# hw2.net
KiCad netlist of a schematic drawn in EAGLE
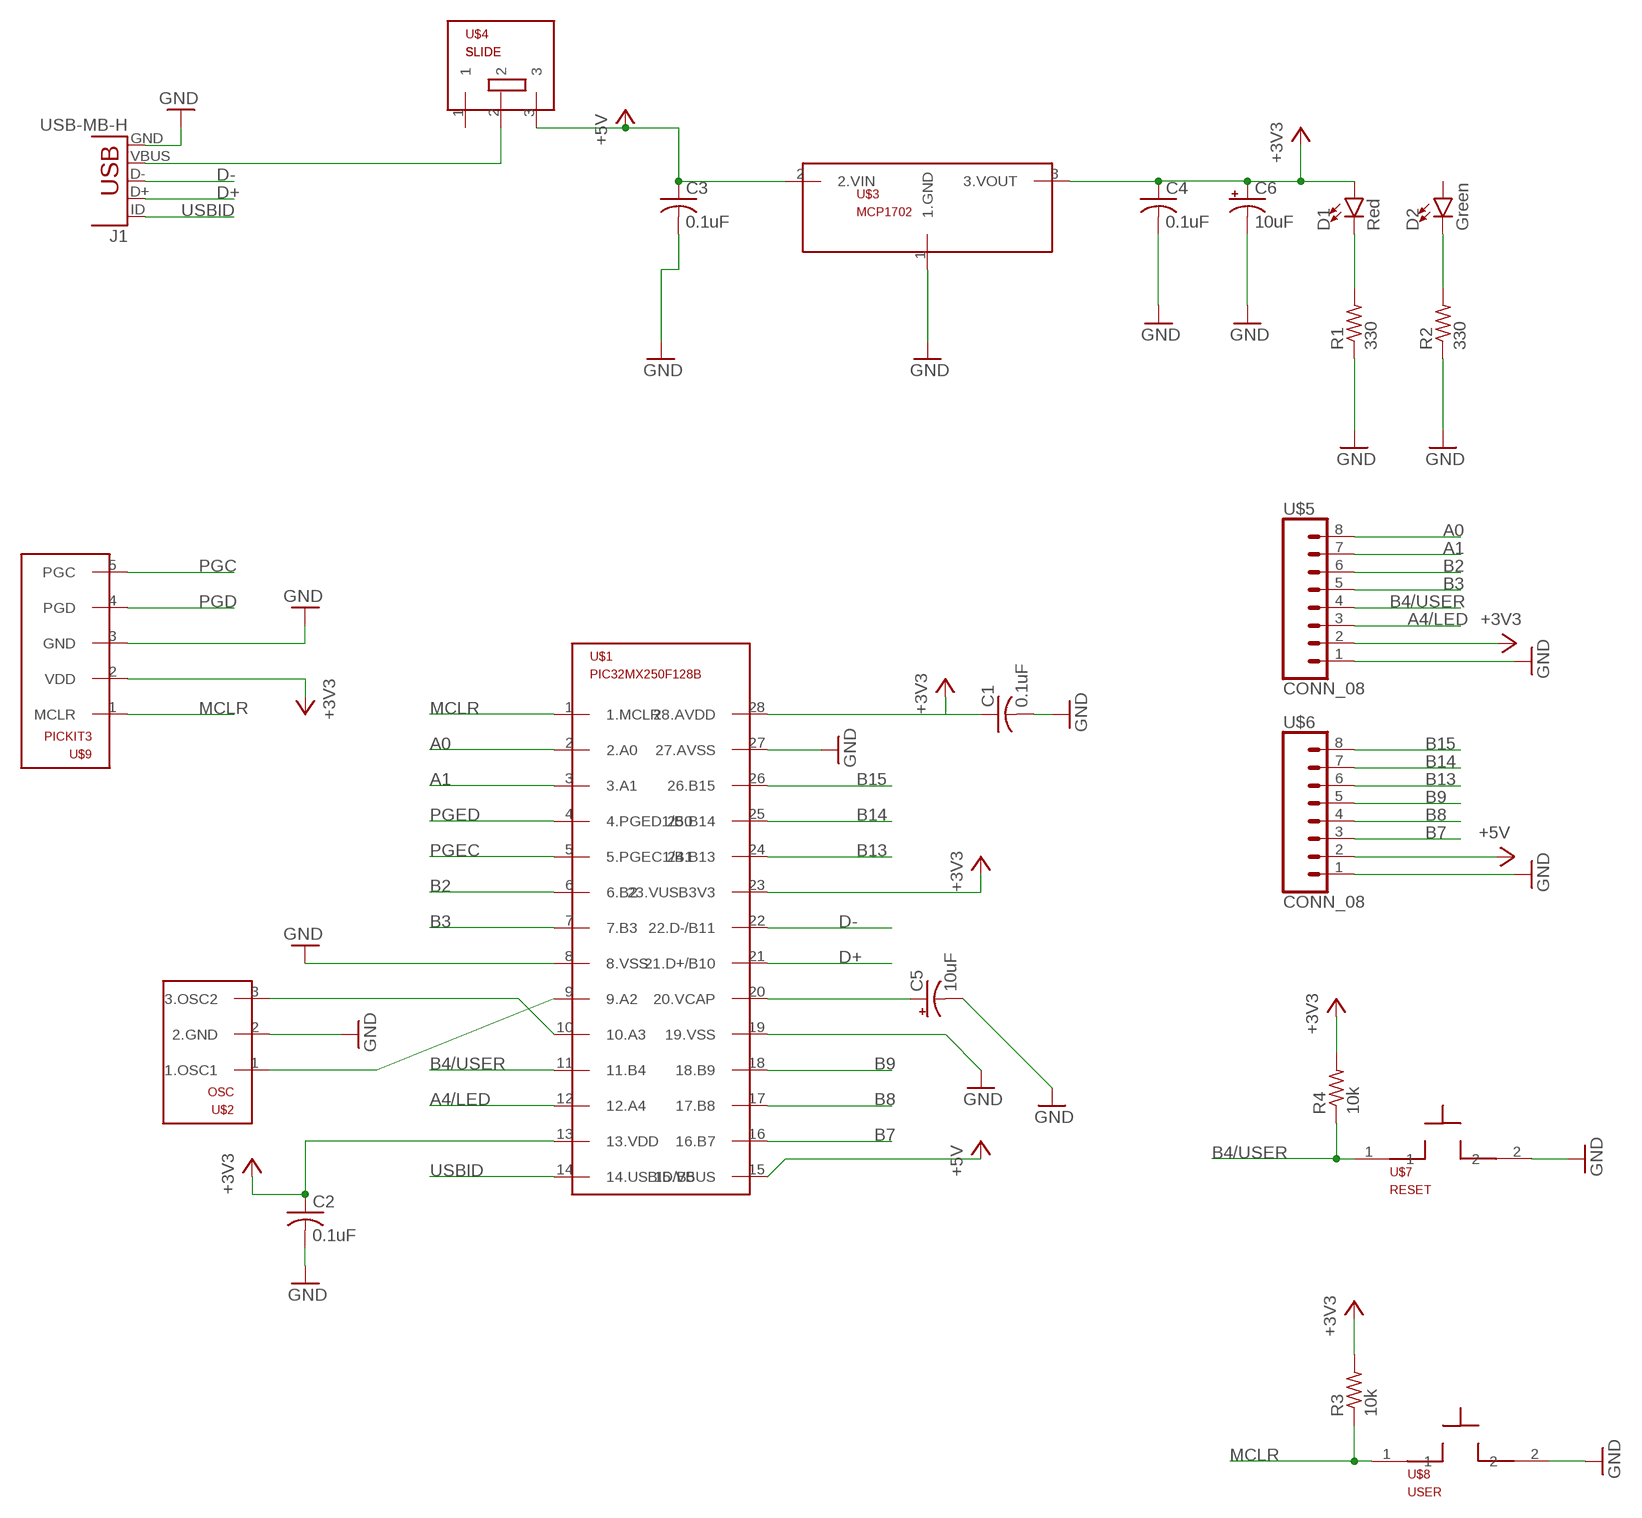
[diagram p0: schematic, sheet 1]

(export (version "E")
  (design (tool "Eeschema 10.0.6"))
  (components
    (comp (ref "C1")
      (value "0.1uF")
      (footprint "eagle-import:C025-025X050")
      (libsource (lib "eagle-import") (part "C-US025-025X050"))
    )
    (comp (ref "C2")
      (value "0.1uF")
      (footprint "eagle-import:C025-025X050")
      (libsource (lib "eagle-import") (part "C-US025-025X050"))
    )
    (comp (ref "C3")
      (value "0.1uF")
      (footprint "eagle-import:C025-025X050")
      (fields (field (name "SPICEPREFIX") "0.1uF"))
      (libsource (lib "eagle-import") (part "C-US025-025X050"))
    )
    (comp (ref "C4")
      (value "0.1uF")
      (footprint "eagle-import:C025-025X050")
      (libsource (lib "eagle-import") (part "C-US025-025X050"))
    )
    (comp (ref "C5")
      (value "10uF")
      (footprint "eagle-import:B45181B")
      (libsource (lib "eagle-import") (part "CPOL-USB45181B"))
    )
    (comp (ref "C6")
      (value "10uF")
      (footprint "eagle-import:B45181B")
      (libsource (lib "eagle-import") (part "CPOL-USB45181B"))
    )
    (comp (ref "D1")
      (value "Red")
      (footprint "eagle-import:LED_3MM")
      (libsource (lib "eagle-import") (part "LED3MM"))
    )
    (comp (ref "D2")
      (value "Green")
      (footprint "eagle-import:LED_3MM")
      (libsource (lib "eagle-import") (part "LED3MM"))
    )
    (comp (ref "J1")
      (value "USB-MB-H")
      (footprint "eagle-import:USB-MB-H")
      (libsource (lib "eagle-import") (part "USB-MB-H"))
    )
    (comp (ref "R1")
      (value "330")
      (footprint "eagle-import:0207_10")
      (libsource (lib "eagle-import") (part "R-US_0207/10"))
    )
    (comp (ref "R2")
      (value "330")
      (footprint "eagle-import:0207_10")
      (libsource (lib "eagle-import") (part "R-US_0207/10"))
    )
    (comp (ref "R3")
      (value "10k")
      (footprint "eagle-import:0207_10")
      (libsource (lib "eagle-import") (part "R-US_0207/10"))
    )
    (comp (ref "R4")
      (value "10k")
      (footprint "eagle-import:0207_10")
      (libsource (lib "eagle-import") (part "R-US_0207/10"))
    )
    (comp (ref "U$1")
      (value "PIC32MX250F128B")
      (footprint "eagle-import:DIL28-3")
      (libsource (lib "eagle-import") (part "PIC32MX250F128B"))
    )
    (comp (ref "U$2")
      (value "OSC")
      (footprint "eagle-import:OSC")
      (libsource (lib "eagle-import") (part "OSC"))
    )
    (comp (ref "U$3")
      (value "MCP1702")
      (footprint "eagle-import:TO92")
      (libsource (lib "eagle-import") (part "MCP1702"))
    )
    (comp (ref "U$4")
      (value "SLIDE")
      (footprint "eagle-import:SLIDE")
      (libsource (lib "eagle-import") (part "SLIDE"))
    )
    (comp (ref "U$5")
      (value "CONN_08")
      (footprint "eagle-import:1X08")
      (libsource (lib "eagle-import") (part "CONN_08"))
    )
    (comp (ref "U$6")
      (value "CONN_08")
      (footprint "eagle-import:1X08")
      (libsource (lib "eagle-import") (part "CONN_08"))
    )
    (comp (ref "U$7")
      (value "RESET")
      (footprint "eagle-import:PB")
      (libsource (lib "eagle-import") (part "PB"))
    )
    (comp (ref "U$8")
      (value "USER")
      (footprint "eagle-import:PB")
      (libsource (lib "eagle-import") (part "PB"))
    )
    (comp (ref "U$9")
      (value "PICKIT3")
      (footprint "eagle-import:1X05")
      (libsource (lib "eagle-import") (part "PICKIT3"))
    )
  )
  (nets
    (net (code "1") (name "+3V3") (class "Default")
      (node (ref "C2") (pin "1") (pinfunction "1_1") (pintype "passive"))
      (node (ref "C4") (pin "1") (pinfunction "1_1") (pintype "passive"))
      (node (ref "C6") (pin "+") (pinfunction "+_+") (pintype "passive"))
      (node (ref "D1") (pin "A") (pinfunction "A_A") (pintype "passive"))
      (node (ref "R3") (pin "2") (pinfunction "2_2") (pintype "passive"))
      (node (ref "R4") (pin "2") (pinfunction "2_2") (pintype "passive"))
      (node (ref "U$1") (pin "13") (pinfunction "13.VDD_13") (pintype "bidirectional"))
      (node (ref "U$1") (pin "23") (pinfunction "23.VUSB3V3_23") (pintype "bidirectional"))
      (node (ref "U$3") (pin "3") (pinfunction "3.VOUT_3") (pintype "bidirectional"))
      (node (ref "U$5") (pin "2") (pinfunction "2_2") (pintype "passive"))
      (node (ref "U$9") (pin "2") (pinfunction "VDD_2") (pintype "bidirectional"))
    )
    (net (code "2") (name "+5V") (class "Default")
      (node (ref "C3") (pin "1") (pinfunction "1_1") (pintype "passive"))
      (node (ref "U$1") (pin "15") (pinfunction "15.VBUS_15") (pintype "bidirectional"))
      (node (ref "U$3") (pin "2") (pinfunction "2.VIN_2") (pintype "bidirectional"))
      (node (ref "U$4") (pin "3") (pinfunction "3_3") (pintype "bidirectional"))
      (node (ref "U$6") (pin "2") (pinfunction "2_2") (pintype "passive"))
    )
    (net (code "3") (name "/A0") (class "Default")
      (node (ref "U$1") (pin "2") (pinfunction "2.A0_2") (pintype "bidirectional"))
      (node (ref "U$5") (pin "8") (pinfunction "8_8") (pintype "passive"))
    )
    (net (code "4") (name "/A1") (class "Default")
      (node (ref "U$1") (pin "3") (pinfunction "3.A1_3") (pintype "bidirectional"))
      (node (ref "U$5") (pin "7") (pinfunction "7_7") (pintype "passive"))
    )
    (net (code "5") (name "/A4{slash}LED") (class "Default")
      (node (ref "U$1") (pin "12") (pinfunction "12.A4_12") (pintype "bidirectional"))
      (node (ref "U$5") (pin "3") (pinfunction "3_3") (pintype "passive"))
    )
    (net (code "6") (name "/B2") (class "Default")
      (node (ref "U$1") (pin "6") (pinfunction "6.B2_6") (pintype "bidirectional"))
      (node (ref "U$5") (pin "6") (pinfunction "6_6") (pintype "passive"))
    )
    (net (code "7") (name "/B3") (class "Default")
      (node (ref "U$1") (pin "7") (pinfunction "7.B3_7") (pintype "bidirectional"))
      (node (ref "U$5") (pin "5") (pinfunction "5_5") (pintype "passive"))
    )
    (net (code "8") (name "/B4{slash}USER") (class "Default")
      (node (ref "R4") (pin "1") (pinfunction "1_1") (pintype "passive"))
      (node (ref "U$1") (pin "11") (pinfunction "11.B4_11") (pintype "bidirectional"))
      (node (ref "U$5") (pin "4") (pinfunction "4_4") (pintype "passive"))
      (node (ref "U$7") (pin "1") (pinfunction "1_1") (pintype "bidirectional"))
    )
    (net (code "9") (name "/B7") (class "Default")
      (node (ref "U$1") (pin "16") (pinfunction "16.B7_16") (pintype "bidirectional"))
      (node (ref "U$6") (pin "3") (pinfunction "3_3") (pintype "passive"))
    )
    (net (code "10") (name "/B8") (class "Default")
      (node (ref "U$1") (pin "17") (pinfunction "17.B8_17") (pintype "bidirectional"))
      (node (ref "U$6") (pin "4") (pinfunction "4_4") (pintype "passive"))
    )
    (net (code "11") (name "/B9") (class "Default")
      (node (ref "U$1") (pin "18") (pinfunction "18.B9_18") (pintype "bidirectional"))
      (node (ref "U$6") (pin "5") (pinfunction "5_5") (pintype "passive"))
    )
    (net (code "12") (name "/B13") (class "Default")
      (node (ref "U$1") (pin "24") (pinfunction "24.B13_24") (pintype "bidirectional"))
      (node (ref "U$6") (pin "6") (pinfunction "6_6") (pintype "passive"))
    )
    (net (code "13") (name "/B14") (class "Default")
      (node (ref "U$1") (pin "25") (pinfunction "25.B14_25") (pintype "bidirectional"))
      (node (ref "U$6") (pin "7") (pinfunction "7_7") (pintype "passive"))
    )
    (net (code "14") (name "/B15") (class "Default")
      (node (ref "U$1") (pin "26") (pinfunction "26.B15_26") (pintype "bidirectional"))
      (node (ref "U$6") (pin "8") (pinfunction "8_8") (pintype "passive"))
    )
    (net (code "15") (name "/D+") (class "Default")
      (node (ref "J1") (pin "D+") (pinfunction "D+_D+") (pintype "bidirectional"))
      (node (ref "U$1") (pin "21") (pinfunction "21.D+/B10_21") (pintype "bidirectional"))
    )
    (net (code "16") (name "/D-") (class "Default")
      (node (ref "J1") (pin "D-") (pinfunction "D-_D-") (pintype "bidirectional"))
      (node (ref "U$1") (pin "22") (pinfunction "22.D-/B11_22") (pintype "bidirectional"))
    )
    (net (code "17") (name "/MCLR") (class "Default")
      (node (ref "R3") (pin "1") (pinfunction "1_1") (pintype "passive"))
      (node (ref "U$1") (pin "1") (pinfunction "1.MCLR_1") (pintype "bidirectional"))
      (node (ref "U$8") (pin "1") (pinfunction "1_1") (pintype "bidirectional"))
      (node (ref "U$9") (pin "1") (pinfunction "MCLR_1") (pintype "bidirectional"))
    )
    (net (code "18") (name "/PGC") (class "Default")
      (node (ref "U$9") (pin "5") (pinfunction "PGC_5") (pintype "bidirectional"))
    )
    (net (code "19") (name "/PGD") (class "Default")
      (node (ref "U$9") (pin "4") (pinfunction "PGD_4") (pintype "bidirectional"))
    )
    (net (code "20") (name "/PGEC") (class "Default")
      (node (ref "U$1") (pin "5") (pinfunction "5.PGEC1/B1_5") (pintype "bidirectional"))
    )
    (net (code "21") (name "/PGED") (class "Default")
      (node (ref "U$1") (pin "4") (pinfunction "4.PGED1/B0_4") (pintype "bidirectional"))
    )
    (net (code "22") (name "/USBID") (class "Default")
      (node (ref "J1") (pin "ID") (pinfunction "ID_ID") (pintype "bidirectional"))
      (node (ref "U$1") (pin "14") (pinfunction "14.USBID/B5_14") (pintype "bidirectional"))
    )
    (net (code "23") (name "GND") (class "Default")
      (node (ref "C1") (pin "2") (pinfunction "2_2") (pintype "passive"))
      (node (ref "C2") (pin "2") (pinfunction "2_2") (pintype "passive"))
      (node (ref "C3") (pin "2") (pinfunction "2_2") (pintype "passive"))
      (node (ref "C4") (pin "2") (pinfunction "2_2") (pintype "passive"))
      (node (ref "C5") (pin "-") (pinfunction "-_-") (pintype "passive"))
      (node (ref "C6") (pin "-") (pinfunction "-_-") (pintype "passive"))
      (node (ref "J1") (pin "GND") (pinfunction "GND_GND") (pintype "bidirectional"))
      (node (ref "R1") (pin "1") (pinfunction "1_1") (pintype "passive"))
      (node (ref "R2") (pin "1") (pinfunction "1_1") (pintype "passive"))
      (node (ref "U$1") (pin "19") (pinfunction "19.VSS_19") (pintype "bidirectional"))
      (node (ref "U$1") (pin "27") (pinfunction "27.AVSS_27") (pintype "bidirectional"))
      (node (ref "U$1") (pin "8") (pinfunction "8.VSS_8") (pintype "bidirectional"))
      (node (ref "U$2") (pin "2") (pinfunction "2.GND_2") (pintype "bidirectional"))
      (node (ref "U$3") (pin "1") (pinfunction "1.GND_1") (pintype "bidirectional"))
      (node (ref "U$5") (pin "1") (pinfunction "1_1") (pintype "passive"))
      (node (ref "U$6") (pin "1") (pinfunction "1_1") (pintype "passive"))
      (node (ref "U$7") (pin "2") (pinfunction "2_2") (pintype "bidirectional"))
      (node (ref "U$8") (pin "2") (pinfunction "2_2") (pintype "bidirectional"))
      (node (ref "U$9") (pin "3") (pinfunction "GND_3") (pintype "bidirectional"))
    )
    (net (code "24") (name "Net-(D1-C)") (class "Default")
      (node (ref "D1") (pin "K") (pinfunction "C_K") (pintype "passive"))
      (node (ref "R1") (pin "2") (pinfunction "2_2") (pintype "passive"))
    )
    (net (code "25") (name "Net-(D2-C)") (class "Default")
      (node (ref "D2") (pin "K") (pinfunction "C_K") (pintype "passive"))
      (node (ref "R2") (pin "2") (pinfunction "2_2") (pintype "passive"))
    )
    (net (code "26") (name "Net-(J1-PadVBUS)") (class "Default")
      (node (ref "J1") (pin "VBUS") (pinfunction "VBUS_VBUS") (pintype "bidirectional"))
      (node (ref "U$4") (pin "2") (pinfunction "2_2") (pintype "bidirectional"))
    )
    (net (code "27") (name "Net-(U$1-9.A2)") (class "Default")
      (node (ref "U$1") (pin "9") (pinfunction "9.A2_9") (pintype "bidirectional"))
      (node (ref "U$2") (pin "1") (pinfunction "1.OSC1_1") (pintype "bidirectional"))
    )
    (net (code "28") (name "Net-(U$1-10.A3)") (class "Default")
      (node (ref "U$1") (pin "10") (pinfunction "10.A3_10") (pintype "bidirectional"))
      (node (ref "U$2") (pin "3") (pinfunction "3.OSC2_3") (pintype "bidirectional"))
    )
    (net (code "29") (name "Net-(U$1-20.VCAP)") (class "Default")
      (node (ref "C5") (pin "+") (pinfunction "+_+") (pintype "passive"))
      (node (ref "U$1") (pin "20") (pinfunction "20.VCAP_20") (pintype "bidirectional"))
    )
    (net (code "30") (name "Net-(U$1-28.AVDD)") (class "Default")
      (node (ref "C1") (pin "1") (pinfunction "1_1") (pintype "passive"))
      (node (ref "U$1") (pin "28") (pinfunction "28.AVDD_28") (pintype "bidirectional"))
    )
    (net (code "31") (name "unconnected-(D2-PadA)") (class "Default")
      (node (ref "D2") (pin "A") (pinfunction "A_A") (pintype "passive"))
    )
    (net (code "32") (name "unconnected-(U$4-Pad1)") (class "Default")
      (node (ref "U$4") (pin "1") (pinfunction "1_1") (pintype "bidirectional"))
    )
  )
)
